# MotorControllerBoard.net
KiCad netlist of a schematic drawn in Altium Designer
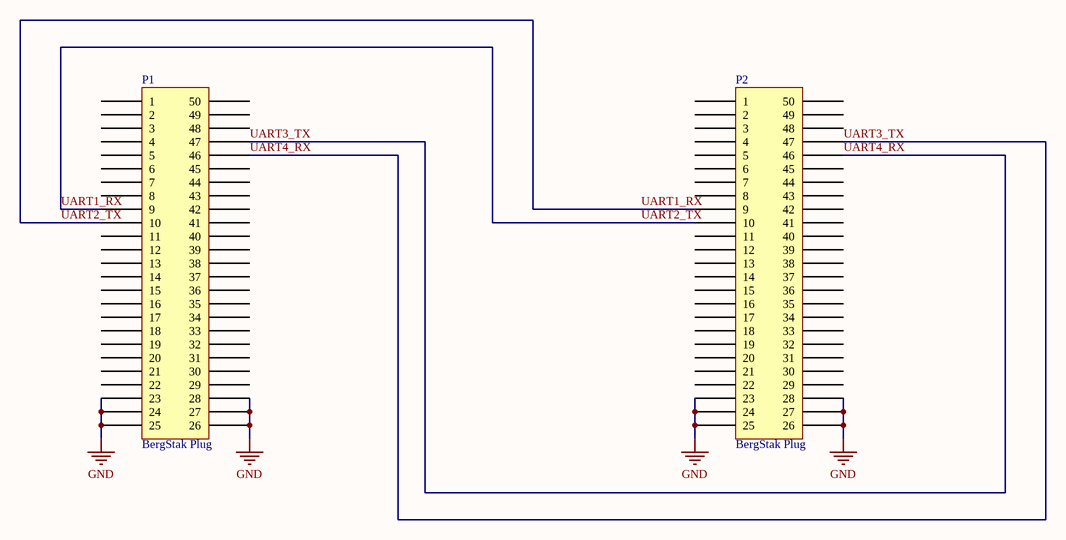
[diagram p0: MotorControllerBoard.SchDoc]

(export (version "E")
  (design (tool "Eeschema 10.0.6"))
  (components
    (comp (ref "P1")
      (value "BergStak Plug")
      (footprint "609-5226-1-ND")
      (description "50 Position Connector Plug, Outer Shroud Contacts Surface Mount Gold")
      (libsource (lib "Schematic Diagrams") (part "BergStak 50 Position Connector Plug"))
    )
    (comp (ref "P2")
      (value "BergStak Plug")
      (footprint "609-5226-1-ND")
      (description "50 Position Connector Plug, Outer Shroud Contacts Surface Mount Gold")
      (libsource (lib "Schematic Diagrams") (part "BergStak 50 Position Connector Plug"))
    )
  )
  (nets
    (net (code "1") (name "/UART1_RX") (class "Default")
      (node (ref "P1") (pin "10") (pinfunction "10_10") (pintype "passive"))
      (node (ref "P1") (pin "9") (pinfunction "9_9") (pintype "passive"))
      (node (ref "P2") (pin "10") (pinfunction "10_10") (pintype "passive"))
      (node (ref "P2") (pin "9") (pinfunction "9_9") (pintype "passive"))
    )
    (net (code "2") (name "/UART3_TX") (class "Default")
      (node (ref "P1") (pin "46") (pinfunction "46_46") (pintype "passive"))
      (node (ref "P1") (pin "47") (pinfunction "47_47") (pintype "passive"))
      (node (ref "P2") (pin "46") (pinfunction "46_46") (pintype "passive"))
      (node (ref "P2") (pin "47") (pinfunction "47_47") (pintype "passive"))
    )
    (net (code "3") (name "GND") (class "Default")
      (node (ref "P1") (pin "23") (pinfunction "23_23") (pintype "passive"))
      (node (ref "P1") (pin "24") (pinfunction "24_24") (pintype "passive"))
      (node (ref "P1") (pin "25") (pinfunction "25_25") (pintype "passive"))
      (node (ref "P1") (pin "26") (pinfunction "26_26") (pintype "passive"))
      (node (ref "P1") (pin "27") (pinfunction "27_27") (pintype "passive"))
      (node (ref "P1") (pin "28") (pinfunction "28_28") (pintype "passive"))
      (node (ref "P2") (pin "23") (pinfunction "23_23") (pintype "passive"))
      (node (ref "P2") (pin "24") (pinfunction "24_24") (pintype "passive"))
      (node (ref "P2") (pin "25") (pinfunction "25_25") (pintype "passive"))
      (node (ref "P2") (pin "26") (pinfunction "26_26") (pintype "passive"))
      (node (ref "P2") (pin "27") (pinfunction "27_27") (pintype "passive"))
      (node (ref "P2") (pin "28") (pinfunction "28_28") (pintype "passive"))
    )
    (net (code "4") (name "unconnected-(P1-Pad1)") (class "Default")
      (node (ref "P1") (pin "1") (pinfunction "1_1") (pintype "passive"))
    )
    (net (code "5") (name "unconnected-(P1-Pad2)") (class "Default")
      (node (ref "P1") (pin "2") (pinfunction "2_2") (pintype "passive"))
    )
    (net (code "6") (name "unconnected-(P1-Pad3)") (class "Default")
      (node (ref "P1") (pin "3") (pinfunction "3_3") (pintype "passive"))
    )
    (net (code "7") (name "unconnected-(P1-Pad4)") (class "Default")
      (node (ref "P1") (pin "4") (pinfunction "4_4") (pintype "passive"))
    )
    (net (code "8") (name "unconnected-(P1-Pad5)") (class "Default")
      (node (ref "P1") (pin "5") (pinfunction "5_5") (pintype "passive"))
    )
    (net (code "9") (name "unconnected-(P1-Pad6)") (class "Default")
      (node (ref "P1") (pin "6") (pinfunction "6_6") (pintype "passive"))
    )
    (net (code "10") (name "unconnected-(P1-Pad7)") (class "Default")
      (node (ref "P1") (pin "7") (pinfunction "7_7") (pintype "passive"))
    )
    (net (code "11") (name "unconnected-(P1-Pad8)") (class "Default")
      (node (ref "P1") (pin "8") (pinfunction "8_8") (pintype "passive"))
    )
    (net (code "12") (name "unconnected-(P1-Pad11)") (class "Default")
      (node (ref "P1") (pin "11") (pinfunction "11_11") (pintype "passive"))
    )
    (net (code "13") (name "unconnected-(P1-Pad12)") (class "Default")
      (node (ref "P1") (pin "12") (pinfunction "12_12") (pintype "passive"))
    )
    (net (code "14") (name "unconnected-(P1-Pad13)") (class "Default")
      (node (ref "P1") (pin "13") (pinfunction "13_13") (pintype "passive"))
    )
    (net (code "15") (name "unconnected-(P1-Pad14)") (class "Default")
      (node (ref "P1") (pin "14") (pinfunction "14_14") (pintype "passive"))
    )
    (net (code "16") (name "unconnected-(P1-Pad15)") (class "Default")
      (node (ref "P1") (pin "15") (pinfunction "15_15") (pintype "passive"))
    )
    (net (code "17") (name "unconnected-(P1-Pad16)") (class "Default")
      (node (ref "P1") (pin "16") (pinfunction "16_16") (pintype "passive"))
    )
    (net (code "18") (name "unconnected-(P1-Pad17)") (class "Default")
      (node (ref "P1") (pin "17") (pinfunction "17_17") (pintype "passive"))
    )
    (net (code "19") (name "unconnected-(P1-Pad18)") (class "Default")
      (node (ref "P1") (pin "18") (pinfunction "18_18") (pintype "passive"))
    )
    (net (code "20") (name "unconnected-(P1-Pad19)") (class "Default")
      (node (ref "P1") (pin "19") (pinfunction "19_19") (pintype "passive"))
    )
    (net (code "21") (name "unconnected-(P1-Pad20)") (class "Default")
      (node (ref "P1") (pin "20") (pinfunction "20_20") (pintype "passive"))
    )
    (net (code "22") (name "unconnected-(P1-Pad21)") (class "Default")
      (node (ref "P1") (pin "21") (pinfunction "21_21") (pintype "passive"))
    )
    (net (code "23") (name "unconnected-(P1-Pad22)") (class "Default")
      (node (ref "P1") (pin "22") (pinfunction "22_22") (pintype "passive"))
    )
    (net (code "24") (name "unconnected-(P1-Pad29)") (class "Default")
      (node (ref "P1") (pin "29") (pinfunction "29_29") (pintype "passive"))
    )
    (net (code "25") (name "unconnected-(P1-Pad30)") (class "Default")
      (node (ref "P1") (pin "30") (pinfunction "30_30") (pintype "passive"))
    )
    (net (code "26") (name "unconnected-(P1-Pad31)") (class "Default")
      (node (ref "P1") (pin "31") (pinfunction "31_31") (pintype "passive"))
    )
    (net (code "27") (name "unconnected-(P1-Pad32)") (class "Default")
      (node (ref "P1") (pin "32") (pinfunction "32_32") (pintype "passive"))
    )
    (net (code "28") (name "unconnected-(P1-Pad33)") (class "Default")
      (node (ref "P1") (pin "33") (pinfunction "33_33") (pintype "passive"))
    )
    (net (code "29") (name "unconnected-(P1-Pad34)") (class "Default")
      (node (ref "P1") (pin "34") (pinfunction "34_34") (pintype "passive"))
    )
    (net (code "30") (name "unconnected-(P1-Pad35)") (class "Default")
      (node (ref "P1") (pin "35") (pinfunction "35_35") (pintype "passive"))
    )
    (net (code "31") (name "unconnected-(P1-Pad36)") (class "Default")
      (node (ref "P1") (pin "36") (pinfunction "36_36") (pintype "passive"))
    )
    (net (code "32") (name "unconnected-(P1-Pad37)") (class "Default")
      (node (ref "P1") (pin "37") (pinfunction "37_37") (pintype "passive"))
    )
    (net (code "33") (name "unconnected-(P1-Pad38)") (class "Default")
      (node (ref "P1") (pin "38") (pinfunction "38_38") (pintype "passive"))
    )
    (net (code "34") (name "unconnected-(P1-Pad39)") (class "Default")
      (node (ref "P1") (pin "39") (pinfunction "39_39") (pintype "passive"))
    )
    (net (code "35") (name "unconnected-(P1-Pad40)") (class "Default")
      (node (ref "P1") (pin "40") (pinfunction "40_40") (pintype "passive"))
    )
    (net (code "36") (name "unconnected-(P1-Pad41)") (class "Default")
      (node (ref "P1") (pin "41") (pinfunction "41_41") (pintype "passive"))
    )
    (net (code "37") (name "unconnected-(P1-Pad42)") (class "Default")
      (node (ref "P1") (pin "42") (pinfunction "42_42") (pintype "passive"))
    )
    (net (code "38") (name "unconnected-(P1-Pad43)") (class "Default")
      (node (ref "P1") (pin "43") (pinfunction "43_43") (pintype "passive"))
    )
    (net (code "39") (name "unconnected-(P1-Pad44)") (class "Default")
      (node (ref "P1") (pin "44") (pinfunction "44_44") (pintype "passive"))
    )
    (net (code "40") (name "unconnected-(P1-Pad45)") (class "Default")
      (node (ref "P1") (pin "45") (pinfunction "45_45") (pintype "passive"))
    )
    (net (code "41") (name "unconnected-(P1-Pad48)") (class "Default")
      (node (ref "P1") (pin "48") (pinfunction "48_48") (pintype "passive"))
    )
    (net (code "42") (name "unconnected-(P1-Pad49)") (class "Default")
      (node (ref "P1") (pin "49") (pinfunction "49_49") (pintype "passive"))
    )
    (net (code "43") (name "unconnected-(P1-Pad50)") (class "Default")
      (node (ref "P1") (pin "50") (pinfunction "50_50") (pintype "passive"))
    )
    (net (code "44") (name "unconnected-(P2-Pad1)") (class "Default")
      (node (ref "P2") (pin "1") (pinfunction "1_1") (pintype "passive"))
    )
    (net (code "45") (name "unconnected-(P2-Pad2)") (class "Default")
      (node (ref "P2") (pin "2") (pinfunction "2_2") (pintype "passive"))
    )
    (net (code "46") (name "unconnected-(P2-Pad3)") (class "Default")
      (node (ref "P2") (pin "3") (pinfunction "3_3") (pintype "passive"))
    )
    (net (code "47") (name "unconnected-(P2-Pad4)") (class "Default")
      (node (ref "P2") (pin "4") (pinfunction "4_4") (pintype "passive"))
    )
    (net (code "48") (name "unconnected-(P2-Pad5)") (class "Default")
      (node (ref "P2") (pin "5") (pinfunction "5_5") (pintype "passive"))
    )
    (net (code "49") (name "unconnected-(P2-Pad6)") (class "Default")
      (node (ref "P2") (pin "6") (pinfunction "6_6") (pintype "passive"))
    )
    (net (code "50") (name "unconnected-(P2-Pad7)") (class "Default")
      (node (ref "P2") (pin "7") (pinfunction "7_7") (pintype "passive"))
    )
    (net (code "51") (name "unconnected-(P2-Pad8)") (class "Default")
      (node (ref "P2") (pin "8") (pinfunction "8_8") (pintype "passive"))
    )
    (net (code "52") (name "unconnected-(P2-Pad11)") (class "Default")
      (node (ref "P2") (pin "11") (pinfunction "11_11") (pintype "passive"))
    )
    (net (code "53") (name "unconnected-(P2-Pad12)") (class "Default")
      (node (ref "P2") (pin "12") (pinfunction "12_12") (pintype "passive"))
    )
    (net (code "54") (name "unconnected-(P2-Pad13)") (class "Default")
      (node (ref "P2") (pin "13") (pinfunction "13_13") (pintype "passive"))
    )
    (net (code "55") (name "unconnected-(P2-Pad14)") (class "Default")
      (node (ref "P2") (pin "14") (pinfunction "14_14") (pintype "passive"))
    )
    (net (code "56") (name "unconnected-(P2-Pad15)") (class "Default")
      (node (ref "P2") (pin "15") (pinfunction "15_15") (pintype "passive"))
    )
    (net (code "57") (name "unconnected-(P2-Pad16)") (class "Default")
      (node (ref "P2") (pin "16") (pinfunction "16_16") (pintype "passive"))
    )
    (net (code "58") (name "unconnected-(P2-Pad17)") (class "Default")
      (node (ref "P2") (pin "17") (pinfunction "17_17") (pintype "passive"))
    )
    (net (code "59") (name "unconnected-(P2-Pad18)") (class "Default")
      (node (ref "P2") (pin "18") (pinfunction "18_18") (pintype "passive"))
    )
    (net (code "60") (name "unconnected-(P2-Pad19)") (class "Default")
      (node (ref "P2") (pin "19") (pinfunction "19_19") (pintype "passive"))
    )
    (net (code "61") (name "unconnected-(P2-Pad20)") (class "Default")
      (node (ref "P2") (pin "20") (pinfunction "20_20") (pintype "passive"))
    )
    (net (code "62") (name "unconnected-(P2-Pad21)") (class "Default")
      (node (ref "P2") (pin "21") (pinfunction "21_21") (pintype "passive"))
    )
    (net (code "63") (name "unconnected-(P2-Pad22)") (class "Default")
      (node (ref "P2") (pin "22") (pinfunction "22_22") (pintype "passive"))
    )
    (net (code "64") (name "unconnected-(P2-Pad29)") (class "Default")
      (node (ref "P2") (pin "29") (pinfunction "29_29") (pintype "passive"))
    )
    (net (code "65") (name "unconnected-(P2-Pad30)") (class "Default")
      (node (ref "P2") (pin "30") (pinfunction "30_30") (pintype "passive"))
    )
    (net (code "66") (name "unconnected-(P2-Pad31)") (class "Default")
      (node (ref "P2") (pin "31") (pinfunction "31_31") (pintype "passive"))
    )
    (net (code "67") (name "unconnected-(P2-Pad32)") (class "Default")
      (node (ref "P2") (pin "32") (pinfunction "32_32") (pintype "passive"))
    )
    (net (code "68") (name "unconnected-(P2-Pad33)") (class "Default")
      (node (ref "P2") (pin "33") (pinfunction "33_33") (pintype "passive"))
    )
    (net (code "69") (name "unconnected-(P2-Pad34)") (class "Default")
      (node (ref "P2") (pin "34") (pinfunction "34_34") (pintype "passive"))
    )
    (net (code "70") (name "unconnected-(P2-Pad35)") (class "Default")
      (node (ref "P2") (pin "35") (pinfunction "35_35") (pintype "passive"))
    )
    (net (code "71") (name "unconnected-(P2-Pad36)") (class "Default")
      (node (ref "P2") (pin "36") (pinfunction "36_36") (pintype "passive"))
    )
    (net (code "72") (name "unconnected-(P2-Pad37)") (class "Default")
      (node (ref "P2") (pin "37") (pinfunction "37_37") (pintype "passive"))
    )
    (net (code "73") (name "unconnected-(P2-Pad38)") (class "Default")
      (node (ref "P2") (pin "38") (pinfunction "38_38") (pintype "passive"))
    )
    (net (code "74") (name "unconnected-(P2-Pad39)") (class "Default")
      (node (ref "P2") (pin "39") (pinfunction "39_39") (pintype "passive"))
    )
    (net (code "75") (name "unconnected-(P2-Pad40)") (class "Default")
      (node (ref "P2") (pin "40") (pinfunction "40_40") (pintype "passive"))
    )
    (net (code "76") (name "unconnected-(P2-Pad41)") (class "Default")
      (node (ref "P2") (pin "41") (pinfunction "41_41") (pintype "passive"))
    )
    (net (code "77") (name "unconnected-(P2-Pad42)") (class "Default")
      (node (ref "P2") (pin "42") (pinfunction "42_42") (pintype "passive"))
    )
    (net (code "78") (name "unconnected-(P2-Pad43)") (class "Default")
      (node (ref "P2") (pin "43") (pinfunction "43_43") (pintype "passive"))
    )
    (net (code "79") (name "unconnected-(P2-Pad44)") (class "Default")
      (node (ref "P2") (pin "44") (pinfunction "44_44") (pintype "passive"))
    )
    (net (code "80") (name "unconnected-(P2-Pad45)") (class "Default")
      (node (ref "P2") (pin "45") (pinfunction "45_45") (pintype "passive"))
    )
    (net (code "81") (name "unconnected-(P2-Pad48)") (class "Default")
      (node (ref "P2") (pin "48") (pinfunction "48_48") (pintype "passive"))
    )
    (net (code "82") (name "unconnected-(P2-Pad49)") (class "Default")
      (node (ref "P2") (pin "49") (pinfunction "49_49") (pintype "passive"))
    )
    (net (code "83") (name "unconnected-(P2-Pad50)") (class "Default")
      (node (ref "P2") (pin "50") (pinfunction "50_50") (pintype "passive"))
    )
  )
)
